# AmpSwitchAutomatic_main.net
KiCad netlist of a schematic drawn in EAGLE
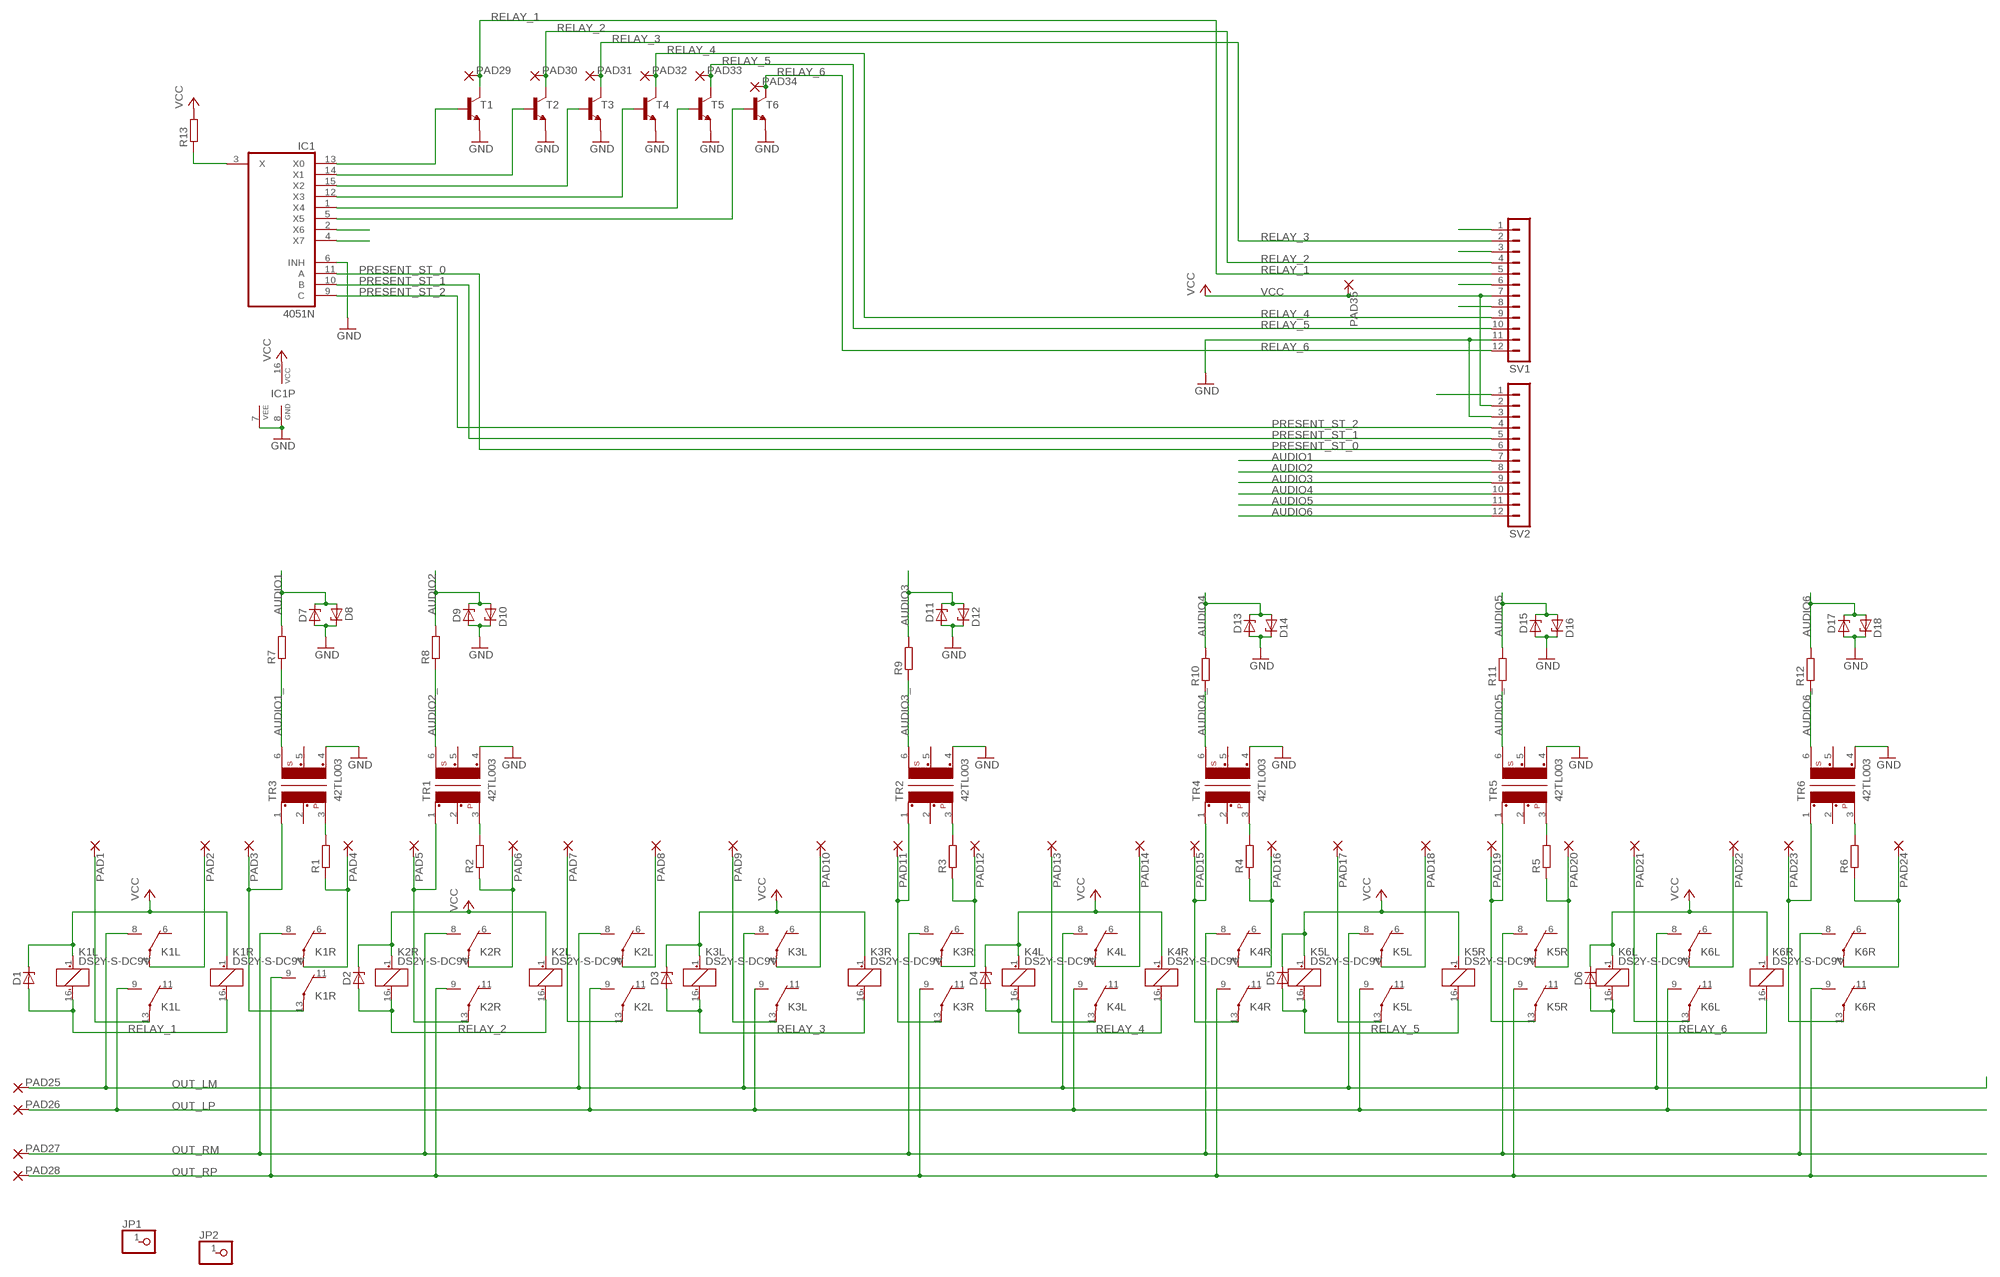
[diagram p0: schematic, sheet 1]

(export (version "E")
  (design (tool "Eeschema 10.0.6"))
  (components
    (comp (ref "D1")
      (value "ZENER-DIODEZD-5")
      (footprint "eagle-import:ZDIO-5")
      (libsource (lib "eagle-import") (part "ZENER-DIODEZD-5"))
    )
    (comp (ref "D2")
      (value "ZENER-DIODEZD-7.5")
      (footprint "eagle-import:ZDIO-7.5")
      (libsource (lib "eagle-import") (part "ZENER-DIODEZD-7.5"))
    )
    (comp (ref "D3")
      (value "ZENER-DIODEZD-12.5")
      (footprint "eagle-import:ZDIO12.5")
      (libsource (lib "eagle-import") (part "ZENER-DIODEZD-12.5"))
    )
    (comp (ref "D4")
      (value "ZENER-DIODEZD-5")
      (footprint "eagle-import:ZDIO-5")
      (libsource (lib "eagle-import") (part "ZENER-DIODEZD-5"))
    )
    (comp (ref "D5")
      (value "ZENER-DIODEZD-5")
      (footprint "eagle-import:ZDIO-5")
      (libsource (lib "eagle-import") (part "ZENER-DIODEZD-5"))
    )
    (comp (ref "D6")
      (value "ZENER-DIODEZD-12.5")
      (footprint "eagle-import:ZDIO12.5")
      (libsource (lib "eagle-import") (part "ZENER-DIODEZD-12.5"))
    )
    (comp (ref "D7")
      (value "ZENER-DIODEZD-7.5")
      (footprint "eagle-import:ZDIO-7.5")
      (libsource (lib "eagle-import") (part "ZENER-DIODEZD-7.5"))
    )
    (comp (ref "D8")
      (value "ZENER-DIODEZD-7.5")
      (footprint "eagle-import:ZDIO-7.5")
      (libsource (lib "eagle-import") (part "ZENER-DIODEZD-7.5"))
    )
    (comp (ref "D9")
      (value "ZENER-DIODEZD-7.5")
      (footprint "eagle-import:ZDIO-7.5")
      (libsource (lib "eagle-import") (part "ZENER-DIODEZD-7.5"))
    )
    (comp (ref "D10")
      (value "ZENER-DIODEZD-7.5")
      (footprint "eagle-import:ZDIO-7.5")
      (libsource (lib "eagle-import") (part "ZENER-DIODEZD-7.5"))
    )
    (comp (ref "D11")
      (value "ZENER-DIODEZD-7.5")
      (footprint "eagle-import:ZDIO-7.5")
      (libsource (lib "eagle-import") (part "ZENER-DIODEZD-7.5"))
    )
    (comp (ref "D12")
      (value "ZENER-DIODEZD-7.5")
      (footprint "eagle-import:ZDIO-7.5")
      (libsource (lib "eagle-import") (part "ZENER-DIODEZD-7.5"))
    )
    (comp (ref "D13")
      (value "ZENER-DIODEZD-7.5")
      (footprint "eagle-import:ZDIO-7.5")
      (libsource (lib "eagle-import") (part "ZENER-DIODEZD-7.5"))
    )
    (comp (ref "D14")
      (value "ZENER-DIODEZD-7.5")
      (footprint "eagle-import:ZDIO-7.5")
      (libsource (lib "eagle-import") (part "ZENER-DIODEZD-7.5"))
    )
    (comp (ref "D15")
      (value "ZENER-DIODEZD-7.5")
      (footprint "eagle-import:ZDIO-7.5")
      (libsource (lib "eagle-import") (part "ZENER-DIODEZD-7.5"))
    )
    (comp (ref "D16")
      (value "ZENER-DIODEZD-7.5")
      (footprint "eagle-import:ZDIO-7.5")
      (libsource (lib "eagle-import") (part "ZENER-DIODEZD-7.5"))
    )
    (comp (ref "D17")
      (value "ZENER-DIODEZD-7.5")
      (footprint "eagle-import:ZDIO-7.5")
      (libsource (lib "eagle-import") (part "ZENER-DIODEZD-7.5"))
    )
    (comp (ref "D18")
      (value "ZENER-DIODEZD-7.5")
      (footprint "eagle-import:ZDIO-7.5")
      (libsource (lib "eagle-import") (part "ZENER-DIODEZD-7.5"))
    )
    (comp (ref "IC1")
      (value "4051N")
      (footprint "eagle-import:DIL16")
      (libsource (lib "eagle-import") (part "4051N"))
    )
    (comp (ref "JP1")
      (value "PINHD-1X1")
      (footprint "eagle-import:1X01")
      (libsource (lib "eagle-import") (part "PINHD-1X1"))
    )
    (comp (ref "JP2")
      (value "PINHD-1X1")
      (footprint "eagle-import:1X01")
      (libsource (lib "eagle-import") (part "PINHD-1X1"))
    )
    (comp (ref "K1L")
      (value "DS2Y-S-DC9V")
      (footprint "eagle-import:DS2Y")
      (libsource (lib "eagle-import") (part "DS2Y-S-DC9V"))
    )
    (comp (ref "K1R")
      (value "DS2Y-S-DC9V")
      (footprint "eagle-import:DS2Y")
      (fields
        (field (name "MPN") "DS2Y-S-DC9V")
        (field (name "OC_FARNELL") "unknown")
        (field (name "OC_NEWARK") "13P3272")
      )
      (libsource (lib "eagle-import") (part "DS2Y-S-DC9V"))
    )
    (comp (ref "K2L")
      (value "DS2Y-S-DC9V")
      (footprint "eagle-import:DS2Y")
      (fields
        (field (name "MPN") "DS2Y-S-DC9V")
        (field (name "OC_FARNELL") "unknown")
        (field (name "OC_NEWARK") "13P3272")
      )
      (libsource (lib "eagle-import") (part "DS2Y-S-DC9V"))
    )
    (comp (ref "K2R")
      (value "DS2Y-S-DC9V")
      (footprint "eagle-import:DS2Y")
      (fields
        (field (name "MPN") "DS2Y-S-DC9V")
        (field (name "OC_FARNELL") "unknown")
        (field (name "OC_NEWARK") "13P3272")
      )
      (libsource (lib "eagle-import") (part "DS2Y-S-DC9V"))
    )
    (comp (ref "K3L")
      (value "DS2Y-S-DC9V")
      (footprint "eagle-import:DS2Y")
      (fields
        (field (name "MPN") "DS2Y-S-DC9V")
        (field (name "OC_FARNELL") "unknown")
        (field (name "OC_NEWARK") "13P3272")
      )
      (libsource (lib "eagle-import") (part "DS2Y-S-DC9V"))
    )
    (comp (ref "K3R")
      (value "DS2Y-S-DC9V")
      (footprint "eagle-import:DS2Y")
      (fields
        (field (name "MPN") "DS2Y-S-DC9V")
        (field (name "OC_FARNELL") "unknown")
        (field (name "OC_NEWARK") "13P3272")
      )
      (libsource (lib "eagle-import") (part "DS2Y-S-DC9V"))
    )
    (comp (ref "K4L")
      (value "DS2Y-S-DC9V")
      (footprint "eagle-import:DS2Y")
      (fields
        (field (name "MPN") "DS2Y-S-DC9V")
        (field (name "OC_FARNELL") "unknown")
        (field (name "OC_NEWARK") "13P3272")
      )
      (libsource (lib "eagle-import") (part "DS2Y-S-DC9V"))
    )
    (comp (ref "K4R")
      (value "DS2Y-S-DC9V")
      (footprint "eagle-import:DS2Y")
      (fields
        (field (name "MPN") "DS2Y-S-DC9V")
        (field (name "OC_FARNELL") "unknown")
        (field (name "OC_NEWARK") "13P3272")
      )
      (libsource (lib "eagle-import") (part "DS2Y-S-DC9V"))
    )
    (comp (ref "K5L")
      (value "DS2Y-S-DC9V")
      (footprint "eagle-import:DS2Y")
      (fields
        (field (name "MPN") "DS2Y-S-DC9V")
        (field (name "OC_FARNELL") "unknown")
        (field (name "OC_NEWARK") "13P3272")
      )
      (libsource (lib "eagle-import") (part "DS2Y-S-DC9V"))
    )
    (comp (ref "K5R")
      (value "DS2Y-S-DC9V")
      (footprint "eagle-import:DS2Y")
      (fields
        (field (name "MPN") "DS2Y-S-DC9V")
        (field (name "OC_FARNELL") "unknown")
        (field (name "OC_NEWARK") "13P3272")
      )
      (libsource (lib "eagle-import") (part "DS2Y-S-DC9V"))
    )
    (comp (ref "K6L")
      (value "DS2Y-S-DC9V")
      (footprint "eagle-import:DS2Y")
      (fields
        (field (name "MPN") "DS2Y-S-DC9V")
        (field (name "OC_FARNELL") "unknown")
        (field (name "OC_NEWARK") "13P3272")
      )
      (libsource (lib "eagle-import") (part "DS2Y-S-DC9V"))
    )
    (comp (ref "K6R")
      (value "DS2Y-S-DC9V")
      (footprint "eagle-import:DS2Y")
      (fields
        (field (name "MPN") "DS2Y-S-DC9V")
        (field (name "OC_FARNELL") "unknown")
        (field (name "OC_NEWARK") "13P3272")
      )
      (libsource (lib "eagle-import") (part "DS2Y-S-DC9V"))
    )
    (comp (ref "PAD1")
      (value "WIREPAD2,15/1,0")
      (footprint "eagle-import:2,15_1,0")
      (libsource (lib "eagle-import") (part "WIREPAD2,15/1,0"))
    )
    (comp (ref "PAD2")
      (value "WIREPAD2,15/1,0")
      (footprint "eagle-import:2,15_1,0")
      (libsource (lib "eagle-import") (part "WIREPAD2,15/1,0"))
    )
    (comp (ref "PAD3")
      (value "WIREPAD2,15/1,0")
      (footprint "eagle-import:2,15_1,0")
      (libsource (lib "eagle-import") (part "WIREPAD2,15/1,0"))
    )
    (comp (ref "PAD4")
      (value "WIREPAD2,15/1,0")
      (footprint "eagle-import:2,15_1,0")
      (libsource (lib "eagle-import") (part "WIREPAD2,15/1,0"))
    )
    (comp (ref "PAD5")
      (value "WIREPAD2,15/1,0")
      (footprint "eagle-import:2,15_1,0")
      (libsource (lib "eagle-import") (part "WIREPAD2,15/1,0"))
    )
    (comp (ref "PAD6")
      (value "WIREPAD2,15/1,0")
      (footprint "eagle-import:2,15_1,0")
      (libsource (lib "eagle-import") (part "WIREPAD2,15/1,0"))
    )
    (comp (ref "PAD7")
      (value "WIREPAD2,15/1,0")
      (footprint "eagle-import:2,15_1,0")
      (libsource (lib "eagle-import") (part "WIREPAD2,15/1,0"))
    )
    (comp (ref "PAD8")
      (value "WIREPAD2,15/1,0")
      (footprint "eagle-import:2,15_1,0")
      (libsource (lib "eagle-import") (part "WIREPAD2,15/1,0"))
    )
    (comp (ref "PAD9")
      (value "WIREPAD2,15/1,0")
      (footprint "eagle-import:2,15_1,0")
      (libsource (lib "eagle-import") (part "WIREPAD2,15/1,0"))
    )
    (comp (ref "PAD10")
      (value "WIREPAD2,15/1,0")
      (footprint "eagle-import:2,15_1,0")
      (libsource (lib "eagle-import") (part "WIREPAD2,15/1,0"))
    )
    (comp (ref "PAD11")
      (value "WIREPAD2,15/1,0")
      (footprint "eagle-import:2,15_1,0")
      (libsource (lib "eagle-import") (part "WIREPAD2,15/1,0"))
    )
    (comp (ref "PAD12")
      (value "WIREPAD2,15/1,0")
      (footprint "eagle-import:2,15_1,0")
      (libsource (lib "eagle-import") (part "WIREPAD2,15/1,0"))
    )
    (comp (ref "PAD13")
      (value "WIREPAD2,15/1,0")
      (footprint "eagle-import:2,15_1,0")
      (libsource (lib "eagle-import") (part "WIREPAD2,15/1,0"))
    )
    (comp (ref "PAD14")
      (value "WIREPAD2,15/1,0")
      (footprint "eagle-import:2,15_1,0")
      (libsource (lib "eagle-import") (part "WIREPAD2,15/1,0"))
    )
    (comp (ref "PAD15")
      (value "WIREPAD2,15/1,0")
      (footprint "eagle-import:2,15_1,0")
      (libsource (lib "eagle-import") (part "WIREPAD2,15/1,0"))
    )
    (comp (ref "PAD16")
      (value "WIREPAD2,15/1,0")
      (footprint "eagle-import:2,15_1,0")
      (libsource (lib "eagle-import") (part "WIREPAD2,15/1,0"))
    )
    (comp (ref "PAD17")
      (value "WIREPAD2,15/1,0")
      (footprint "eagle-import:2,15_1,0")
      (libsource (lib "eagle-import") (part "WIREPAD2,15/1,0"))
    )
    (comp (ref "PAD18")
      (value "WIREPAD2,15/1,0")
      (footprint "eagle-import:2,15_1,0")
      (libsource (lib "eagle-import") (part "WIREPAD2,15/1,0"))
    )
    (comp (ref "PAD19")
      (value "WIREPAD2,15/1,0")
      (footprint "eagle-import:2,15_1,0")
      (libsource (lib "eagle-import") (part "WIREPAD2,15/1,0"))
    )
    (comp (ref "PAD20")
      (value "WIREPAD2,15/1,0")
      (footprint "eagle-import:2,15_1,0")
      (libsource (lib "eagle-import") (part "WIREPAD2,15/1,0"))
    )
    (comp (ref "PAD21")
      (value "WIREPAD2,15/1,0")
      (footprint "eagle-import:2,15_1,0")
      (libsource (lib "eagle-import") (part "WIREPAD2,15/1,0"))
    )
    (comp (ref "PAD22")
      (value "WIREPAD2,15/1,0")
      (footprint "eagle-import:2,15_1,0")
      (libsource (lib "eagle-import") (part "WIREPAD2,15/1,0"))
    )
    (comp (ref "PAD23")
      (value "WIREPAD2,15/1,0")
      (footprint "eagle-import:2,15_1,0")
      (libsource (lib "eagle-import") (part "WIREPAD2,15/1,0"))
    )
    (comp (ref "PAD24")
      (value "WIREPAD2,15/1,0")
      (footprint "eagle-import:2,15_1,0")
      (libsource (lib "eagle-import") (part "WIREPAD2,15/1,0"))
    )
    (comp (ref "PAD25")
      (value "WIREPAD2,15/1,0")
      (footprint "eagle-import:2,15_1,0")
      (libsource (lib "eagle-import") (part "WIREPAD2,15/1,0"))
    )
    (comp (ref "PAD26")
      (value "WIREPAD2,15/1,0")
      (footprint "eagle-import:2,15_1,0")
      (libsource (lib "eagle-import") (part "WIREPAD2,15/1,0"))
    )
    (comp (ref "PAD27")
      (value "WIREPAD2,15/1,0")
      (footprint "eagle-import:2,15_1,0")
      (libsource (lib "eagle-import") (part "WIREPAD2,15/1,0"))
    )
    (comp (ref "PAD28")
      (value "WIREPAD2,15/1,0")
      (footprint "eagle-import:2,15_1,0")
      (libsource (lib "eagle-import") (part "WIREPAD2,15/1,0"))
    )
    (comp (ref "PAD29")
      (value "WIREPAD2,15/1,0")
      (footprint "eagle-import:2,15_1,0")
      (libsource (lib "eagle-import") (part "WIREPAD2,15/1,0"))
    )
    (comp (ref "PAD30")
      (value "WIREPAD2,15/1,0")
      (footprint "eagle-import:2,15_1,0")
      (libsource (lib "eagle-import") (part "WIREPAD2,15/1,0"))
    )
    (comp (ref "PAD31")
      (value "WIREPAD2,15/1,0")
      (footprint "eagle-import:2,15_1,0")
      (libsource (lib "eagle-import") (part "WIREPAD2,15/1,0"))
    )
    (comp (ref "PAD32")
      (value "WIREPAD2,15/1,0")
      (footprint "eagle-import:2,15_1,0")
      (libsource (lib "eagle-import") (part "WIREPAD2,15/1,0"))
    )
    (comp (ref "PAD33")
      (value "WIREPAD2,15/1,0")
      (footprint "eagle-import:2,15_1,0")
      (libsource (lib "eagle-import") (part "WIREPAD2,15/1,0"))
    )
    (comp (ref "PAD34")
      (value "WIREPAD2,15/1,0")
      (footprint "eagle-import:2,15_1,0")
      (libsource (lib "eagle-import") (part "WIREPAD2,15/1,0"))
    )
    (comp (ref "PAD35")
      (value "WIREPAD2,15/1,0")
      (footprint "eagle-import:2,15_1,0")
      (libsource (lib "eagle-import") (part "WIREPAD2,15/1,0"))
    )
    (comp (ref "R1")
      (value "R-EU_0207/15")
      (footprint "eagle-import:0207_15")
      (libsource (lib "eagle-import") (part "resistor_R-EU_0207/15"))
    )
    (comp (ref "R2")
      (value "R-EU_0207/15")
      (footprint "eagle-import:0207_15")
      (libsource (lib "eagle-import") (part "resistor_R-EU_0207/15"))
    )
    (comp (ref "R3")
      (value "R-EU_0207/15")
      (footprint "eagle-import:0207_15")
      (libsource (lib "eagle-import") (part "resistor_R-EU_0207/15"))
    )
    (comp (ref "R4")
      (value "R-EU_0207/15")
      (footprint "eagle-import:0207_15")
      (libsource (lib "eagle-import") (part "resistor_R-EU_0207/15"))
    )
    (comp (ref "R5")
      (value "R-EU_0207/15")
      (footprint "eagle-import:0207_15")
      (libsource (lib "eagle-import") (part "resistor_R-EU_0207/15"))
    )
    (comp (ref "R6")
      (value "R-EU_0207/15")
      (footprint "eagle-import:0207_15")
      (libsource (lib "eagle-import") (part "resistor_R-EU_0207/15"))
    )
    (comp (ref "R7")
      (value "R-EU_0207/12")
      (footprint "eagle-import:0207_12")
      (libsource (lib "eagle-import") (part "R-EU_0207/12"))
    )
    (comp (ref "R8")
      (value "R-EU_0207/10")
      (footprint "eagle-import:0207_10")
      (libsource (lib "eagle-import") (part "R-EU_0207/10"))
    )
    (comp (ref "R9")
      (value "R-EU_0207/7")
      (footprint "eagle-import:0207_7")
      (libsource (lib "eagle-import") (part "R-EU_0207/7"))
    )
    (comp (ref "R10")
      (value "R-EU_0207/5V")
      (footprint "eagle-import:0207_5V")
      (libsource (lib "eagle-import") (part "R-EU_0207/5V"))
    )
    (comp (ref "R11")
      (value "R-EU_0207/2V")
      (footprint "eagle-import:0207_2V")
      (libsource (lib "eagle-import") (part "R-EU_0207/2V"))
    )
    (comp (ref "R12")
      (value "R-EU_0207/5V")
      (footprint "eagle-import:0207_5V")
      (libsource (lib "eagle-import") (part "R-EU_0207/5V"))
    )
    (comp (ref "R13")
      (value "R-EU_0207/7")
      (footprint "eagle-import:0207_7")
      (libsource (lib "eagle-import") (part "R-EU_0207/7"))
    )
    (comp (ref "SV1")
      (value "MA12-1")
      (footprint "eagle-import:MA12-1")
      (fields (field (name "OC_FARNELL") "unknown") (field (name "OC_NEWARK") "unknown"))
      (libsource (lib "eagle-import") (part "MA12-1"))
    )
    (comp (ref "SV2")
      (value "MA12-1")
      (footprint "eagle-import:MA12-1")
      (fields (field (name "OC_FARNELL") "unknown") (field (name "OC_NEWARK") "unknown"))
      (libsource (lib "eagle-import") (part "MA12-1"))
    )
    (comp (ref "T1")
      (value "2N4124-NPN-TO92-CBE")
      (footprint "eagle-import:TO92-CBE")
      (libsource (lib "eagle-import") (part "-NPN-TO92-CBE2N4124"))
    )
    (comp (ref "T2")
      (value "2N4124-NPN-TO92-CBE")
      (footprint "eagle-import:TO92-CBE")
      (libsource (lib "eagle-import") (part "-NPN-TO92-CBE2N4124"))
    )
    (comp (ref "T3")
      (value "2N4124-NPN-TO92-CBE")
      (footprint "eagle-import:TO92-CBE")
      (libsource (lib "eagle-import") (part "-NPN-TO92-CBE2N4124"))
    )
    (comp (ref "T4")
      (value "2N4124-NPN-TO92-CBE")
      (footprint "eagle-import:TO92-CBE")
      (libsource (lib "eagle-import") (part "-NPN-TO92-CBE2N4124"))
    )
    (comp (ref "T5")
      (value "2N4124-NPN-TO92-CBE")
      (footprint "eagle-import:TO92-CBE")
      (libsource (lib "eagle-import") (part "-NPN-TO92-CBE2N4124"))
    )
    (comp (ref "T6")
      (value "2N4124-NPN-TO92-CBE")
      (footprint "eagle-import:TO92-CBE")
      (libsource (lib "eagle-import") (part "-NPN-TO92-CBE2N4124"))
    )
    (comp (ref "TR1")
      (value "42TL003")
      (footprint "eagle-import:42TL")
      (fields (field (name "OC_FARNELL") "unknown") (field (name "OC_NEWARK") "unknown"))
      (libsource (lib "eagle-import") (part "42T?L003"))
    )
    (comp (ref "TR2")
      (value "42TL003")
      (footprint "eagle-import:42TL")
      (fields (field (name "OC_FARNELL") "unknown") (field (name "OC_NEWARK") "unknown"))
      (libsource (lib "eagle-import") (part "42T?L003"))
    )
    (comp (ref "TR3")
      (value "42TL003")
      (footprint "eagle-import:42TL")
      (libsource (lib "eagle-import") (part "42T?L003"))
    )
    (comp (ref "TR4")
      (value "42TL003")
      (footprint "eagle-import:42TL")
      (fields (field (name "OC_FARNELL") "unknown") (field (name "OC_NEWARK") "unknown"))
      (libsource (lib "eagle-import") (part "42T?L003"))
    )
    (comp (ref "TR5")
      (value "42TL003")
      (footprint "eagle-import:42TL")
      (fields (field (name "OC_FARNELL") "unknown") (field (name "OC_NEWARK") "unknown"))
      (libsource (lib "eagle-import") (part "42T?L003"))
    )
    (comp (ref "TR6")
      (value "42TL003")
      (footprint "eagle-import:42TL")
      (fields (field (name "OC_FARNELL") "unknown") (field (name "OC_NEWARK") "unknown"))
      (libsource (lib "eagle-import") (part "42T?L003"))
    )
  )
  (nets
    (net (code "1") (name "/AUDIO1") (class "Default")
      (node (ref "D7") (pin "C") (pinfunction "C_C") (pintype "passive"))
      (node (ref "D8") (pin "A") (pinfunction "A_A") (pintype "passive"))
      (node (ref "R7") (pin "2") (pinfunction "2_2") (pintype "passive"))
      (node (ref "SV2") (pin "7") (pinfunction "7_7") (pintype "passive"))
    )
    (net (code "2") (name "/AUDIO1_") (class "Default")
      (node (ref "R7") (pin "1") (pinfunction "1_1") (pintype "passive"))
      (node (ref "TR3") (pin "6") (pinfunction "6_6") (pintype "passive"))
    )
    (net (code "3") (name "/AUDIO2") (class "Default")
      (node (ref "D10") (pin "A") (pinfunction "A_A") (pintype "passive"))
      (node (ref "D9") (pin "C") (pinfunction "C_C") (pintype "passive"))
      (node (ref "R8") (pin "2") (pinfunction "2_2") (pintype "passive"))
      (node (ref "SV2") (pin "8") (pinfunction "8_8") (pintype "passive"))
    )
    (net (code "4") (name "/AUDIO2_") (class "Default")
      (node (ref "R8") (pin "1") (pinfunction "1_1") (pintype "passive"))
      (node (ref "TR1") (pin "6") (pinfunction "6_6") (pintype "passive"))
    )
    (net (code "5") (name "/AUDIO3") (class "Default")
      (node (ref "D11") (pin "C") (pinfunction "C_C") (pintype "passive"))
      (node (ref "D12") (pin "A") (pinfunction "A_A") (pintype "passive"))
      (node (ref "R9") (pin "2") (pinfunction "2_2") (pintype "passive"))
      (node (ref "SV2") (pin "9") (pinfunction "9_9") (pintype "passive"))
    )
    (net (code "6") (name "/AUDIO3_") (class "Default")
      (node (ref "R9") (pin "1") (pinfunction "1_1") (pintype "passive"))
      (node (ref "TR2") (pin "6") (pinfunction "6_6") (pintype "passive"))
    )
    (net (code "7") (name "/AUDIO4") (class "Default")
      (node (ref "D13") (pin "C") (pinfunction "C_C") (pintype "passive"))
      (node (ref "D14") (pin "A") (pinfunction "A_A") (pintype "passive"))
      (node (ref "R10") (pin "2") (pinfunction "2_2") (pintype "passive"))
      (node (ref "SV2") (pin "10") (pinfunction "10_10") (pintype "passive"))
    )
    (net (code "8") (name "/AUDIO4_") (class "Default")
      (node (ref "R10") (pin "1") (pinfunction "1_1") (pintype "passive"))
      (node (ref "TR4") (pin "6") (pinfunction "6_6") (pintype "passive"))
    )
    (net (code "9") (name "/AUDIO5") (class "Default")
      (node (ref "D15") (pin "C") (pinfunction "C_C") (pintype "passive"))
      (node (ref "D16") (pin "A") (pinfunction "A_A") (pintype "passive"))
      (node (ref "R11") (pin "2") (pinfunction "2_2") (pintype "passive"))
      (node (ref "SV2") (pin "11") (pinfunction "11_11") (pintype "passive"))
    )
    (net (code "10") (name "/AUDIO5_") (class "Default")
      (node (ref "R11") (pin "1") (pinfunction "1_1") (pintype "passive"))
      (node (ref "TR5") (pin "6") (pinfunction "6_6") (pintype "passive"))
    )
    (net (code "11") (name "/AUDIO6") (class "Default")
      (node (ref "D17") (pin "C") (pinfunction "C_C") (pintype "passive"))
      (node (ref "D18") (pin "A") (pinfunction "A_A") (pintype "passive"))
      (node (ref "R12") (pin "2") (pinfunction "2_2") (pintype "passive"))
      (node (ref "SV2") (pin "12") (pinfunction "12_12") (pintype "passive"))
    )
    (net (code "12") (name "/AUDIO6_") (class "Default")
      (node (ref "R12") (pin "1") (pinfunction "1_1") (pintype "passive"))
      (node (ref "TR6") (pin "6") (pinfunction "6_6") (pintype "passive"))
    )
    (net (code "13") (name "/OUT_LM") (class "Default")
      (node (ref "K1L") (pin "8") (pinfunction "S_8") (pintype "passive"))
      (node (ref "K2L") (pin "8") (pinfunction "S_8") (pintype "passive"))
      (node (ref "K3L") (pin "8") (pinfunction "S_8") (pintype "passive"))
      (node (ref "K4L") (pin "8") (pinfunction "S_8") (pintype "passive"))
      (node (ref "K5L") (pin "8") (pinfunction "S_8") (pintype "passive"))
      (node (ref "K6L") (pin "8") (pinfunction "S_8") (pintype "passive"))
      (node (ref "PAD25") (pin "1") (pinfunction "P_1") (pintype "passive"))
    )
    (net (code "14") (name "/OUT_LP") (class "Default")
      (node (ref "K1L") (pin "9") (pinfunction "S_9") (pintype "passive"))
      (node (ref "K2L") (pin "9") (pinfunction "S_9") (pintype "passive"))
      (node (ref "K3L") (pin "9") (pinfunction "S_9") (pintype "passive"))
      (node (ref "K4L") (pin "9") (pinfunction "S_9") (pintype "passive"))
      (node (ref "K5L") (pin "9") (pinfunction "S_9") (pintype "passive"))
      (node (ref "K6L") (pin "9") (pinfunction "S_9") (pintype "passive"))
      (node (ref "PAD26") (pin "1") (pinfunction "P_1") (pintype "passive"))
    )
    (net (code "15") (name "/OUT_RM") (class "Default")
      (node (ref "K1R") (pin "8") (pinfunction "S_8") (pintype "passive"))
      (node (ref "K2R") (pin "8") (pinfunction "S_8") (pintype "passive"))
      (node (ref "K3R") (pin "8") (pinfunction "S_8") (pintype "passive"))
      (node (ref "K4R") (pin "8") (pinfunction "S_8") (pintype "passive"))
      (node (ref "K5R") (pin "8") (pinfunction "S_8") (pintype "passive"))
      (node (ref "K6R") (pin "8") (pinfunction "S_8") (pintype "passive"))
      (node (ref "PAD27") (pin "1") (pinfunction "P_1") (pintype "passive"))
    )
    (net (code "16") (name "/OUT_RP") (class "Default")
      (node (ref "K1R") (pin "9") (pinfunction "S_9") (pintype "passive"))
      (node (ref "K2R") (pin "9") (pinfunction "S_9") (pintype "passive"))
      (node (ref "K3R") (pin "9") (pinfunction "S_9") (pintype "passive"))
      (node (ref "K4R") (pin "9") (pinfunction "S_9") (pintype "passive"))
      (node (ref "K5R") (pin "9") (pinfunction "S_9") (pintype "passive"))
      (node (ref "K6R") (pin "9") (pinfunction "S_9") (pintype "passive"))
      (node (ref "PAD28") (pin "1") (pinfunction "P_1") (pintype "passive"))
    )
    (net (code "17") (name "/PRESENT_ST_0") (class "Default")
      (node (ref "IC1") (pin "11") (pinfunction "A_11") (pintype "input"))
      (node (ref "SV2") (pin "6") (pinfunction "6_6") (pintype "passive"))
    )
    (net (code "18") (name "/PRESENT_ST_1") (class "Default")
      (node (ref "IC1") (pin "10") (pinfunction "B_10") (pintype "input"))
      (node (ref "SV2") (pin "5") (pinfunction "5_5") (pintype "passive"))
    )
    (net (code "19") (name "/PRESENT_ST_2") (class "Default")
      (node (ref "IC1") (pin "9") (pinfunction "C_9") (pintype "input"))
      (node (ref "SV2") (pin "4") (pinfunction "4_4") (pintype "passive"))
    )
    (net (code "20") (name "/RELAY_1") (class "Default")
      (node (ref "D1") (pin "A") (pinfunction "A_A") (pintype "passive"))
      (node (ref "K1L") (pin "16") (pinfunction "-_16") (pintype "passive"))
      (node (ref "K1R") (pin "16") (pinfunction "-_16") (pintype "passive"))
      (node (ref "PAD29") (pin "1") (pinfunction "P_1") (pintype "passive"))
      (node (ref "SV1") (pin "5") (pinfunction "5_5") (pintype "passive"))
      (node (ref "T1") (pin "C") (pinfunction "C_C") (pintype "passive"))
    )
    (net (code "21") (name "/RELAY_2") (class "Default")
      (node (ref "D2") (pin "A") (pinfunction "A_A") (pintype "passive"))
      (node (ref "K2L") (pin "16") (pinfunction "-_16") (pintype "passive"))
      (node (ref "K2R") (pin "16") (pinfunction "-_16") (pintype "passive"))
      (node (ref "PAD30") (pin "1") (pinfunction "P_1") (pintype "passive"))
      (node (ref "SV1") (pin "4") (pinfunction "4_4") (pintype "passive"))
      (node (ref "T2") (pin "C") (pinfunction "C_C") (pintype "passive"))
    )
    (net (code "22") (name "/RELAY_3") (class "Default")
      (node (ref "D3") (pin "A") (pinfunction "A_A") (pintype "passive"))
      (node (ref "K3L") (pin "16") (pinfunction "-_16") (pintype "passive"))
      (node (ref "K3R") (pin "16") (pinfunction "-_16") (pintype "passive"))
      (node (ref "PAD31") (pin "1") (pinfunction "P_1") (pintype "passive"))
      (node (ref "SV1") (pin "2") (pinfunction "2_2") (pintype "passive"))
      (node (ref "T3") (pin "C") (pinfunction "C_C") (pintype "passive"))
    )
    (net (code "23") (name "/RELAY_4") (class "Default")
      (node (ref "D4") (pin "A") (pinfunction "A_A") (pintype "passive"))
      (node (ref "K4L") (pin "16") (pinfunction "-_16") (pintype "passive"))
      (node (ref "K4R") (pin "16") (pinfunction "-_16") (pintype "passive"))
      (node (ref "PAD32") (pin "1") (pinfunction "P_1") (pintype "passive"))
      (node (ref "SV1") (pin "9") (pinfunction "9_9") (pintype "passive"))
      (node (ref "T4") (pin "C") (pinfunction "C_C") (pintype "passive"))
    )
    (net (code "24") (name "/RELAY_5") (class "Default")
      (node (ref "D5") (pin "A") (pinfunction "A_A") (pintype "passive"))
      (node (ref "K5L") (pin "16") (pinfunction "-_16") (pintype "passive"))
      (node (ref "K5R") (pin "16") (pinfunction "-_16") (pintype "passive"))
      (node (ref "PAD33") (pin "1") (pinfunction "P_1") (pintype "passive"))
      (node (ref "SV1") (pin "10") (pinfunction "10_10") (pintype "passive"))
      (node (ref "T5") (pin "C") (pinfunction "C_C") (pintype "passive"))
    )
    (net (code "25") (name "/RELAY_6") (class "Default")
      (node (ref "D6") (pin "A") (pinfunction "A_A") (pintype "passive"))
      (node (ref "K6L") (pin "16") (pinfunction "-_16") (pintype "passive"))
      (node (ref "K6R") (pin "16") (pinfunction "-_16") (pintype "passive"))
      (node (ref "PAD34") (pin "1") (pinfunction "P_1") (pintype "passive"))
      (node (ref "SV1") (pin "12") (pinfunction "12_12") (pintype "passive"))
      (node (ref "T6") (pin "C") (pinfunction "C_C") (pintype "passive"))
    )
    (net (code "26") (name "GND") (class "Default")
      (node (ref "D10") (pin "C") (pinfunction "C_C") (pintype "passive"))
      (node (ref "D11") (pin "A") (pinfunction "A_A") (pintype "passive"))
      (node (ref "D12") (pin "C") (pinfunction "C_C") (pintype "passive"))
      (node (ref "D13") (pin "A") (pinfunction "A_A") (pintype "passive"))
      (node (ref "D14") (pin "C") (pinfunction "C_C") (pintype "passive"))
      (node (ref "D15") (pin "A") (pinfunction "A_A") (pintype "passive"))
      (node (ref "D16") (pin "C") (pinfunction "C_C") (pintype "passive"))
      (node (ref "D17") (pin "A") (pinfunction "A_A") (pintype "passive"))
      (node (ref "D18") (pin "C") (pinfunction "C_C") (pintype "passive"))
      (node (ref "D7") (pin "A") (pinfunction "A_A") (pintype "passive"))
      (node (ref "D8") (pin "C") (pinfunction "C_C") (pintype "passive"))
      (node (ref "D9") (pin "A") (pinfunction "A_A") (pintype "passive"))
      (node (ref "IC1") (pin "6") (pinfunction "INH_6") (pintype "input"))
      (node (ref "IC1") (pin "7") (pinfunction "VEE_7") (pintype "power_in"))
      (node (ref "IC1") (pin "8") (pinfunction "GND_8") (pintype "power_in"))
      (node (ref "SV1") (pin "11") (pinfunction "11_11") (pintype "passive"))
      (node (ref "SV2") (pin "3") (pinfunction "3_3") (pintype "passive"))
      (node (ref "T1") (pin "E") (pinfunction "E_E") (pintype "passive"))
      (node (ref "T2") (pin "E") (pinfunction "E_E") (pintype "passive"))
      (node (ref "T3") (pin "E") (pinfunction "E_E") (pintype "passive"))
      (node (ref "T4") (pin "E") (pinfunction "E_E") (pintype "passive"))
      (node (ref "T5") (pin "E") (pinfunction "E_E") (pintype "passive"))
      (node (ref "T6") (pin "E") (pinfunction "E_E") (pintype "passive"))
      (node (ref "TR1") (pin "4") (pinfunction "4_4") (pintype "passive"))
      (node (ref "TR2") (pin "4") (pinfunction "4_4") (pintype "passive"))
      (node (ref "TR3") (pin "4") (pinfunction "4_4") (pintype "passive"))
      (node (ref "TR4") (pin "4") (pinfunction "4_4") (pintype "passive"))
      (node (ref "TR5") (pin "4") (pinfunction "4_4") (pintype "passive"))
      (node (ref "TR6") (pin "4") (pinfunction "4_4") (pintype "passive"))
    )
    (net (code "27") (name "Net-(IC1A-X)") (class "Default")
      (node (ref "IC1") (pin "3") (pinfunction "X_3") (pintype "bidirectional"))
      (node (ref "R13") (pin "1") (pinfunction "1_1") (pintype "passive"))
    )
    (net (code "28") (name "Net-(IC1A-X0)") (class "Default")
      (node (ref "IC1") (pin "13") (pinfunction "X0_13") (pintype "bidirectional"))
      (node (ref "T1") (pin "B") (pinfunction "B_B") (pintype "passive"))
    )
    (net (code "29") (name "Net-(IC1A-X1)") (class "Default")
      (node (ref "IC1") (pin "14") (pinfunction "X1_14") (pintype "bidirectional"))
      (node (ref "T2") (pin "B") (pinfunction "B_B") (pintype "passive"))
    )
    (net (code "30") (name "Net-(IC1A-X2)") (class "Default")
      (node (ref "IC1") (pin "15") (pinfunction "X2_15") (pintype "bidirectional"))
      (node (ref "T3") (pin "B") (pinfunction "B_B") (pintype "passive"))
    )
    (net (code "31") (name "Net-(IC1A-X3)") (class "Default")
      (node (ref "IC1") (pin "12") (pinfunction "X3_12") (pintype "bidirectional"))
      (node (ref "T4") (pin "B") (pinfunction "B_B") (pintype "passive"))
    )
    (net (code "32") (name "Net-(IC1A-X4)") (class "Default")
      (node (ref "IC1") (pin "1") (pinfunction "X4_1") (pintype "bidirectional"))
      (node (ref "T5") (pin "B") (pinfunction "B_B") (pintype "passive"))
    )
    (net (code "33") (name "Net-(IC1A-X5)") (class "Default")
      (node (ref "IC1") (pin "5") (pinfunction "X5_5") (pintype "bidirectional"))
      (node (ref "T6") (pin "B") (pinfunction "B_B") (pintype "passive"))
    )
    (net (code "34") (name "Net-(K1LB-P)") (class "Default")
      (node (ref "K1L") (pin "4") (pinfunction "P_4") (pintype "passive"))
      (node (ref "PAD2") (pin "1") (pinfunction "P_1") (pintype "passive"))
    )
    (net (code "35") (name "Net-(K1LC-P)") (class "Default")
      (node (ref "K1L") (pin "13") (pinfunction "P_13") (pintype "passive"))
      (node (ref "PAD1") (pin "1") (pinfunction "P_1") (pintype "passive"))
    )
    (net (code "36") (name "Net-(K1RB-P)") (class "Default")
      (node (ref "K1R") (pin "4") (pinfunction "P_4") (pintype "passive"))
      (node (ref "PAD4") (pin "1") (pinfunction "P_1") (pintype "passive"))
      (node (ref "R1") (pin "1") (pinfunction "1_1") (pintype "passive"))
    )
    (net (code "37") (name "Net-(K1RC-P)") (class "Default")
      (node (ref "K1R") (pin "13") (pinfunction "P_13") (pintype "passive"))
      (node (ref "PAD3") (pin "1") (pinfunction "P_1") (pintype "passive"))
      (node (ref "TR3") (pin "1") (pinfunction "1_1") (pintype "passive"))
    )
    (net (code "38") (name "Net-(K2LB-P)") (class "Default")
      (node (ref "K2L") (pin "4") (pinfunction "P_4") (pintype "passive"))
      (node (ref "PAD8") (pin "1") (pinfunction "P_1") (pintype "passive"))
    )
    (net (code "39") (name "Net-(K2LC-P)") (class "Default")
      (node (ref "K2L") (pin "13") (pinfunction "P_13") (pintype "passive"))
      (node (ref "PAD7") (pin "1") (pinfunction "P_1") (pintype "passive"))
    )
    (net (code "40") (name "Net-(K2RB-P)") (class "Default")
      (node (ref "K2R") (pin "4") (pinfunction "P_4") (pintype "passive"))
      (node (ref "PAD6") (pin "1") (pinfunction "P_1") (pintype "passive"))
      (node (ref "R2") (pin "1") (pinfunction "1_1") (pintype "passive"))
    )
    (net (code "41") (name "Net-(K2RC-P)") (class "Default")
      (node (ref "K2R") (pin "13") (pinfunction "P_13") (pintype "passive"))
      (node (ref "PAD5") (pin "1") (pinfunction "P_1") (pintype "passive"))
      (node (ref "TR1") (pin "1") (pinfunction "1_1") (pintype "passive"))
    )
    (net (code "42") (name "Net-(K3LB-P)") (class "Default")
      (node (ref "K3L") (pin "4") (pinfunction "P_4") (pintype "passive"))
      (node (ref "PAD10") (pin "1") (pinfunction "P_1") (pintype "passive"))
    )
    (net (code "43") (name "Net-(K3LC-P)") (class "Default")
      (node (ref "K3L") (pin "13") (pinfunction "P_13") (pintype "passive"))
      (node (ref "PAD9") (pin "1") (pinfunction "P_1") (pintype "passive"))
    )
    (net (code "44") (name "Net-(K3RB-P)") (class "Default")
      (node (ref "K3R") (pin "4") (pinfunction "P_4") (pintype "passive"))
      (node (ref "PAD12") (pin "1") (pinfunction "P_1") (pintype "passive"))
      (node (ref "R3") (pin "1") (pinfunction "1_1") (pintype "passive"))
    )
    (net (code "45") (name "Net-(K3RC-P)") (class "Default")
      (node (ref "K3R") (pin "13") (pinfunction "P_13") (pintype "passive"))
      (node (ref "PAD11") (pin "1") (pinfunction "P_1") (pintype "passive"))
      (node (ref "TR2") (pin "1") (pinfunction "1_1") (pintype "passive"))
    )
    (net (code "46") (name "Net-(K4LB-P)") (class "Default")
      (node (ref "K4L") (pin "4") (pinfunction "P_4") (pintype "passive"))
      (node (ref "PAD14") (pin "1") (pinfunction "P_1") (pintype "passive"))
    )
    (net (code "47") (name "Net-(K4LC-P)") (class "Default")
      (node (ref "K4L") (pin "13") (pinfunction "P_13") (pintype "passive"))
      (node (ref "PAD13") (pin "1") (pinfunction "P_1") (pintype "passive"))
    )
    (net (code "48") (name "Net-(K4RB-P)") (class "Default")
      (node (ref "K4R") (pin "4") (pinfunction "P_4") (pintype "passive"))
      (node (ref "PAD16") (pin "1") (pinfunction "P_1") (pintype "passive"))
      (node (ref "R4") (pin "1") (pinfunction "1_1") (pintype "passive"))
    )
    (net (code "49") (name "Net-(K4RC-P)") (class "Default")
      (node (ref "K4R") (pin "13") (pinfunction "P_13") (pintype "passive"))
      (node (ref "PAD15") (pin "1") (pinfunction "P_1") (pintype "passive"))
      (node (ref "TR4") (pin "1") (pinfunction "1_1") (pintype "passive"))
    )
    (net (code "50") (name "Net-(K5LB-P)") (class "Default")
      (node (ref "K5L") (pin "4") (pinfunction "P_4") (pintype "passive"))
      (node (ref "PAD18") (pin "1") (pinfunction "P_1") (pintype "passive"))
    )
    (net (code "51") (name "Net-(K5LC-P)") (class "Default")
      (node (ref "K5L") (pin "13") (pinfunction "P_13") (pintype "passive"))
      (node (ref "PAD17") (pin "1") (pinfunction "P_1") (pintype "passive"))
    )
    (net (code "52") (name "Net-(K5RB-P)") (class "Default")
      (node (ref "K5R") (pin "4") (pinfunction "P_4") (pintype "passive"))
      (node (ref "PAD20") (pin "1") (pinfunction "P_1") (pintype "passive"))
      (node (ref "R5") (pin "1") (pinfunction "1_1") (pintype "passive"))
    )
    (net (code "53") (name "Net-(K5RC-P)") (class "Default")
      (node (ref "K5R") (pin "13") (pinfunction "P_13") (pintype "passive"))
      (node (ref "PAD19") (pin "1") (pinfunction "P_1") (pintype "passive"))
      (node (ref "TR5") (pin "1") (pinfunction "1_1") (pintype "passive"))
    )
    (net (code "54") (name "Net-(K6LB-P)") (class "Default")
      (node (ref "K6L") (pin "4") (pinfunction "P_4") (pintype "passive"))
      (node (ref "PAD22") (pin "1") (pinfunction "P_1") (pintype "passive"))
    )
    (net (code "55") (name "Net-(K6LC-P)") (class "Default")
      (node (ref "K6L") (pin "13") (pinfunction "P_13") (pintype "passive"))
      (node (ref "PAD21") (pin "1") (pinfunction "P_1") (pintype "passive"))
    )
    (net (code "56") (name "Net-(K6RB-P)") (class "Default")
      (node (ref "K6R") (pin "4") (pinfunction "P_4") (pintype "passive"))
      (node (ref "PAD24") (pin "1") (pinfunction "P_1") (pintype "passive"))
      (node (ref "R6") (pin "1") (pinfunction "1_1") (pintype "passive"))
    )
    (net (code "57") (name "Net-(K6RC-P)") (class "Default")
      (node (ref "K6R") (pin "13") (pinfunction "P_13") (pintype "passive"))
      (node (ref "PAD23") (pin "1") (pinfunction "P_1") (pintype "passive"))
      (node (ref "TR6") (pin "1") (pinfunction "1_1") (pintype "passive"))
    )
    (net (code "58") (name "Net-(R1-Pad2)") (class "Default")
      (node (ref "R1") (pin "2") (pinfunction "2_2") (pintype "passive"))
      (node (ref "TR3") (pin "3") (pinfunction "3_3") (pintype "passive"))
    )
    (net (code "59") (name "Net-(R2-Pad2)") (class "Default")
      (node (ref "R2") (pin "2") (pinfunction "2_2") (pintype "passive"))
      (node (ref "TR1") (pin "3") (pinfunction "3_3") (pintype "passive"))
    )
    (net (code "60") (name "Net-(R3-Pad2)") (class "Default")
      (node (ref "R3") (pin "2") (pinfunction "2_2") (pintype "passive"))
      (node (ref "TR2") (pin "3") (pinfunction "3_3") (pintype "passive"))
    )
    (net (code "61") (name "Net-(R4-Pad2)") (class "Default")
      (node (ref "R4") (pin "2") (pinfunction "2_2") (pintype "passive"))
      (node (ref "TR4") (pin "3") (pinfunction "3_3") (pintype "passive"))
    )
    (net (code "62") (name "Net-(R5-Pad2)") (class "Default")
      (node (ref "R5") (pin "2") (pinfunction "2_2") (pintype "passive"))
      (node (ref "TR5") (pin "3") (pinfunction "3_3") (pintype "passive"))
    )
    (net (code "63") (name "Net-(R6-Pad2)") (class "Default")
      (node (ref "R6") (pin "2") (pinfunction "2_2") (pintype "passive"))
      (node (ref "TR6") (pin "3") (pinfunction "3_3") (pintype "passive"))
    )
    (net (code "64") (name "VCC") (class "Default")
      (node (ref "D1") (pin "C") (pinfunction "C_C") (pintype "passive"))
      (node (ref "D2") (pin "C") (pinfunction "C_C") (pintype "passive"))
      (node (ref "D3") (pin "C") (pinfunction "C_C") (pintype "passive"))
      (node (ref "D4") (pin "C") (pinfunction "C_C") (pintype "passive"))
      (node (ref "D5") (pin "C") (pinfunction "C_C") (pintype "passive"))
      (node (ref "D6") (pin "C") (pinfunction "C_C") (pintype "passive"))
      (node (ref "IC1") (pin "16") (pinfunction "VCC_16") (pintype "power_in"))
      (node (ref "K1L") (pin "1") (pinfunction "+_1") (pintype "passive"))
      (node (ref "K1R") (pin "1") (pinfunction "+_1") (pintype "passive"))
      (node (ref "K2L") (pin "1") (pinfunction "+_1") (pintype "passive"))
      (node (ref "K2R") (pin "1") (pinfunction "+_1") (pintype "passive"))
      (node (ref "K3L") (pin "1") (pinfunction "+_1") (pintype "passive"))
      (node (ref "K3R") (pin "1") (pinfunction "+_1") (pintype "passive"))
      (node (ref "K4L") (pin "1") (pinfunction "+_1") (pintype "passive"))
      (node (ref "K4R") (pin "1") (pinfunction "+_1") (pintype "passive"))
      (node (ref "K5L") (pin "1") (pinfunction "+_1") (pintype "passive"))
      (node (ref "K5R") (pin "1") (pinfunction "+_1") (pintype "passive"))
      (node (ref "K6L") (pin "1") (pinfunction "+_1") (pintype "passive"))
      (node (ref "K6R") (pin "1") (pinfunction "+_1") (pintype "passive"))
      (node (ref "PAD35") (pin "1") (pinfunction "P_1") (pintype "passive"))
      (node (ref "R13") (pin "2") (pinfunction "2_2") (pintype "passive"))
      (node (ref "SV1") (pin "7") (pinfunction "7_7") (pintype "passive"))
      (node (ref "SV2") (pin "2") (pinfunction "2_2") (pintype "passive"))
    )
    (net (code "65") (name "unconnected-(IC1A-X6-Pad2)") (class "Default")
      (node (ref "IC1") (pin "2") (pinfunction "X6_2") (pintype "bidirectional"))
    )
    (net (code "66") (name "unconnected-(IC1A-X7-Pad4)") (class "Default")
      (node (ref "IC1") (pin "4") (pinfunction "X7_4") (pintype "bidirectional"))
    )
    (net (code "67") (name "unconnected-(JP1-Pad1)") (class "Default")
      (node (ref "JP1") (pin "1") (pinfunction "1_1") (pintype "passive"))
    )
    (net (code "68") (name "unconnected-(JP2-Pad1)") (class "Default")
      (node (ref "JP2") (pin "1") (pinfunction "1_1") (pintype "passive"))
    )
    (net (code "69") (name "unconnected-(K1LB-O-Pad6)") (class "Default")
      (node (ref "K1L") (pin "6") (pinfunction "O_6") (pintype "passive"))
    )
    (net (code "70") (name "unconnected-(K1LC-O-Pad11)") (class "Default")
      (node (ref "K1L") (pin "11") (pinfunction "O_11") (pintype "passive"))
    )
    (net (code "71") (name "unconnected-(K1RB-O-Pad6)") (class "Default")
      (node (ref "K1R") (pin "6") (pinfunction "O_6") (pintype "passive"))
    )
    (net (code "72") (name "unconnected-(K1RC-O-Pad11)") (class "Default")
      (node (ref "K1R") (pin "11") (pinfunction "O_11") (pintype "passive"))
    )
    (net (code "73") (name "unconnected-(K2LB-O-Pad6)") (class "Default")
      (node (ref "K2L") (pin "6") (pinfunction "O_6") (pintype "passive"))
    )
    (net (code "74") (name "unconnected-(K2LC-O-Pad11)") (class "Default")
      (node (ref "K2L") (pin "11") (pinfunction "O_11") (pintype "passive"))
    )
    (net (code "75") (name "unconnected-(K2RB-O-Pad6)") (class "Default")
      (node (ref "K2R") (pin "6") (pinfunction "O_6") (pintype "passive"))
    )
    (net (code "76") (name "unconnected-(K2RC-O-Pad11)") (class "Default")
      (node (ref "K2R") (pin "11") (pinfunction "O_11") (pintype "passive"))
    )
    (net (code "77") (name "unconnected-(K3LB-O-Pad6)") (class "Default")
      (node (ref "K3L") (pin "6") (pinfunction "O_6") (pintype "passive"))
    )
    (net (code "78") (name "unconnected-(K3LC-O-Pad11)") (class "Default")
      (node (ref "K3L") (pin "11") (pinfunction "O_11") (pintype "passive"))
    )
    (net (code "79") (name "unconnected-(K3RB-O-Pad6)") (class "Default")
      (node (ref "K3R") (pin "6") (pinfunction "O_6") (pintype "passive"))
    )
    (net (code "80") (name "unconnected-(K3RC-O-Pad11)") (class "Default")
      (node (ref "K3R") (pin "11") (pinfunction "O_11") (pintype "passive"))
    )
    (net (code "81") (name "unconnected-(K4LB-O-Pad6)") (class "Default")
      (node (ref "K4L") (pin "6") (pinfunction "O_6") (pintype "passive"))
    )
    (net (code "82") (name "unconnected-(K4LC-O-Pad11)") (class "Default")
      (node (ref "K4L") (pin "11") (pinfunction "O_11") (pintype "passive"))
    )
    (net (code "83") (name "unconnected-(K4RB-O-Pad6)") (class "Default")
      (node (ref "K4R") (pin "6") (pinfunction "O_6") (pintype "passive"))
    )
    (net (code "84") (name "unconnected-(K4RC-O-Pad11)") (class "Default")
      (node (ref "K4R") (pin "11") (pinfunction "O_11") (pintype "passive"))
    )
    (net (code "85") (name "unconnected-(K5LB-O-Pad6)") (class "Default")
      (node (ref "K5L") (pin "6") (pinfunction "O_6") (pintype "passive"))
    )
    (net (code "86") (name "unconnected-(K5LC-O-Pad11)") (class "Default")
      (node (ref "K5L") (pin "11") (pinfunction "O_11") (pintype "passive"))
    )
    (net (code "87") (name "unconnected-(K5RB-O-Pad6)") (class "Default")
      (node (ref "K5R") (pin "6") (pinfunction "O_6") (pintype "passive"))
    )
    (net (code "88") (name "unconnected-(K5RC-O-Pad11)") (class "Default")
      (node (ref "K5R") (pin "11") (pinfunction "O_11") (pintype "passive"))
    )
    (net (code "89") (name "unconnected-(K6LB-O-Pad6)") (class "Default")
      (node (ref "K6L") (pin "6") (pinfunction "O_6") (pintype "passive"))
    )
    (net (code "90") (name "unconnected-(K6LC-O-Pad11)") (class "Default")
      (node (ref "K6L") (pin "11") (pinfunction "O_11") (pintype "passive"))
    )
    (net (code "91") (name "unconnected-(K6RB-O-Pad6)") (class "Default")
      (node (ref "K6R") (pin "6") (pinfunction "O_6") (pintype "passive"))
    )
    (net (code "92") (name "unconnected-(K6RC-O-Pad11)") (class "Default")
      (node (ref "K6R") (pin "11") (pinfunction "O_11") (pintype "passive"))
    )
    (net (code "93") (name "unconnected-(SV1-Pad1)") (class "Default")
      (node (ref "SV1") (pin "1") (pinfunction "1_1") (pintype "passive"))
    )
    (net (code "94") (name "unconnected-(SV1-Pad3)") (class "Default")
      (node (ref "SV1") (pin "3") (pinfunction "3_3") (pintype "passive"))
    )
    (net (code "95") (name "unconnected-(SV1-Pad6)") (class "Default")
      (node (ref "SV1") (pin "6") (pinfunction "6_6") (pintype "passive"))
    )
    (net (code "96") (name "unconnected-(SV1-Pad8)") (class "Default")
      (node (ref "SV1") (pin "8") (pinfunction "8_8") (pintype "passive"))
    )
    (net (code "97") (name "unconnected-(SV2-Pad1)") (class "Default")
      (node (ref "SV2") (pin "1") (pinfunction "1_1") (pintype "passive"))
    )
    (net (code "98") (name "unconnected-(TR1-Pad2)") (class "Default")
      (node (ref "TR1") (pin "2") (pinfunction "2_2") (pintype "passive"))
    )
    (net (code "99") (name "unconnected-(TR1-Pad5)") (class "Default")
      (node (ref "TR1") (pin "5") (pinfunction "5_5") (pintype "passive"))
    )
    (net (code "100") (name "unconnected-(TR2-Pad2)") (class "Default")
      (node (ref "TR2") (pin "2") (pinfunction "2_2") (pintype "passive"))
    )
    (net (code "101") (name "unconnected-(TR2-Pad5)") (class "Default")
      (node (ref "TR2") (pin "5") (pinfunction "5_5") (pintype "passive"))
    )
    (net (code "102") (name "unconnected-(TR3-Pad2)") (class "Default")
      (node (ref "TR3") (pin "2") (pinfunction "2_2") (pintype "passive"))
    )
    (net (code "103") (name "unconnected-(TR3-Pad5)") (class "Default")
      (node (ref "TR3") (pin "5") (pinfunction "5_5") (pintype "passive"))
    )
    (net (code "104") (name "unconnected-(TR4-Pad2)") (class "Default")
      (node (ref "TR4") (pin "2") (pinfunction "2_2") (pintype "passive"))
    )
    (net (code "105") (name "unconnected-(TR4-Pad5)") (class "Default")
      (node (ref "TR4") (pin "5") (pinfunction "5_5") (pintype "passive"))
    )
    (net (code "106") (name "unconnected-(TR5-Pad2)") (class "Default")
      (node (ref "TR5") (pin "2") (pinfunction "2_2") (pintype "passive"))
    )
    (net (code "107") (name "unconnected-(TR5-Pad5)") (class "Default")
      (node (ref "TR5") (pin "5") (pinfunction "5_5") (pintype "passive"))
    )
    (net (code "108") (name "unconnected-(TR6-Pad2)") (class "Default")
      (node (ref "TR6") (pin "2") (pinfunction "2_2") (pintype "passive"))
    )
    (net (code "109") (name "unconnected-(TR6-Pad5)") (class "Default")
      (node (ref "TR6") (pin "5") (pinfunction "5_5") (pintype "passive"))
    )
  )
)
